# PCB_2.net
KiCad netlist of a schematic drawn in EAGLE
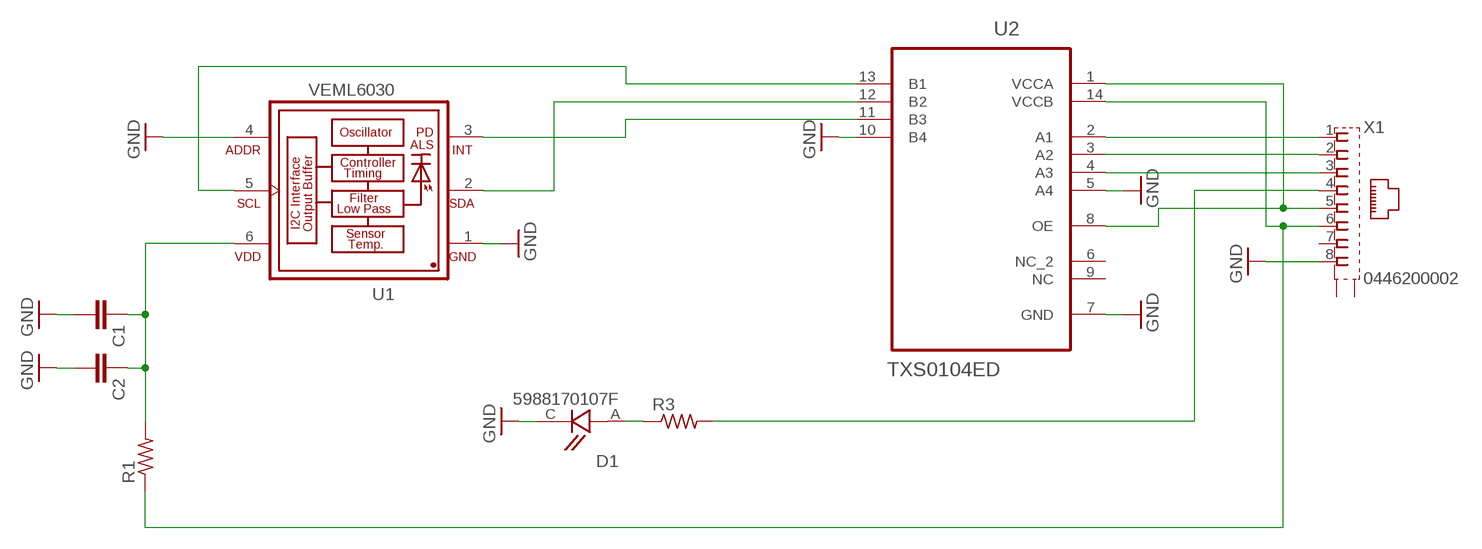
[diagram p0: schematic, sheet 1]

(export (version "E")
  (design (tool "Eeschema 10.0.6"))
  (components
    (comp (ref "C1")
      (value "C-EU025-024X044")
      (footprint "eagle-import:C025-024X044")
      (libsource (lib "eagle-import") (part "C-EU025-024X044"))
    )
    (comp (ref "C2")
      (value "C-EU025-024X044")
      (footprint "eagle-import:C025-024X044")
      (libsource (lib "eagle-import") (part "C-EU025-024X044"))
    )
    (comp (ref "D1")
      (value "5988170107F")
      (footprint "eagle-import:LEDC2012X70N")
      (fields (field (name "MF") "Dialight"))
      (libsource (lib "eagle-import") (part "5988170107F"))
    )
    (comp (ref "R1")
      (value "R-US_R0805")
      (footprint "eagle-import:R0805")
      (libsource (lib "eagle-import") (part "R-US_R0805"))
    )
    (comp (ref "R3")
      (value "R-US_R0805")
      (footprint "eagle-import:R0805")
      (libsource (lib "eagle-import") (part "R-US_R0805"))
    )
    (comp (ref "U1")
      (value "VEML6030")
      (footprint "eagle-import:VISHAY_VEML6030_2X2X0.87")
      (fields (field (name "MF") "Vishay"))
      (libsource (lib "eagle-import") (part "VEML6030"))
    )
    (comp (ref "U2")
      (value "TXS0104ED")
      (footprint "eagle-import:SOIC127P600X175-14N")
      (fields (field (name "MF") "Texas Instruments"))
      (libsource (lib "eagle-import") (part "TXS0104ED"))
    )
    (comp (ref "X1")
      (value "0446200002")
      (footprint "eagle-import:0446200002")
      (fields (field (name "MF") "Molex, LLC"))
      (libsource (lib "eagle-import") (part "0446200002"))
    )
  )
  (nets
    (net (code "1") (name "GND") (class "Default")
      (node (ref "C1") (pin "2") (pinfunction "2_2") (pintype "passive"))
      (node (ref "C2") (pin "2") (pinfunction "2_2") (pintype "passive"))
      (node (ref "D1") (pin "C") (pinfunction "C_C") (pintype "passive"))
      (node (ref "U1") (pin "1") (pinfunction "GND_1") (pintype "power_in"))
      (node (ref "U1") (pin "4") (pinfunction "ADDR_4") (pintype "bidirectional"))
      (node (ref "U2") (pin "10") (pinfunction "B4_10") (pintype "output"))
      (node (ref "U2") (pin "5") (pinfunction "A4_5") (pintype "input"))
      (node (ref "U2") (pin "7") (pinfunction "GND_7") (pintype "passive"))
      (node (ref "X1") (pin "8") (pinfunction "8_8") (pintype "passive"))
    )
    (net (code "2") (name "Net-(D1-PadA)") (class "Default")
      (node (ref "D1") (pin "A") (pinfunction "A_A") (pintype "passive"))
      (node (ref "R3") (pin "1") (pinfunction "1_1") (pintype "passive"))
    )
    (net (code "3") (name "Net-(R3-Pad2)") (class "Default")
      (node (ref "R3") (pin "2") (pinfunction "2_2") (pintype "passive"))
      (node (ref "X1") (pin "4") (pinfunction "4_4") (pintype "passive"))
    )
    (net (code "4") (name "Net-(U1-INT)") (class "Default")
      (node (ref "U1") (pin "3") (pinfunction "INT_3") (pintype "output"))
      (node (ref "U2") (pin "11") (pinfunction "B3_11") (pintype "output"))
    )
    (net (code "5") (name "Net-(U1-SCL)") (class "Default")
      (node (ref "U1") (pin "5") (pinfunction "SCL_5") (pintype "input"))
      (node (ref "U2") (pin "13") (pinfunction "B1_13") (pintype "output"))
    )
    (net (code "6") (name "Net-(U1-SDA)") (class "Default")
      (node (ref "U1") (pin "2") (pinfunction "SDA_2") (pintype "bidirectional"))
      (node (ref "U2") (pin "12") (pinfunction "B2_12") (pintype "output"))
    )
    (net (code "7") (name "Net-(U1-VDD)") (class "Default")
      (node (ref "C1") (pin "1") (pinfunction "1_1") (pintype "passive"))
      (node (ref "C2") (pin "1") (pinfunction "1_1") (pintype "passive"))
      (node (ref "R1") (pin "2") (pinfunction "2_2") (pintype "passive"))
      (node (ref "U1") (pin "6") (pinfunction "VDD_6") (pintype "power_in"))
    )
    (net (code "8") (name "Net-(U2-A1)") (class "Default")
      (node (ref "U2") (pin "2") (pinfunction "A1_2") (pintype "input"))
      (node (ref "X1") (pin "1") (pinfunction "1_1") (pintype "passive"))
    )
    (net (code "9") (name "Net-(U2-A2)") (class "Default")
      (node (ref "U2") (pin "3") (pinfunction "A2_3") (pintype "input"))
      (node (ref "X1") (pin "2") (pinfunction "2_2") (pintype "passive"))
    )
    (net (code "10") (name "Net-(U2-A3)") (class "Default")
      (node (ref "U2") (pin "4") (pinfunction "A3_4") (pintype "input"))
      (node (ref "X1") (pin "3") (pinfunction "3_3") (pintype "passive"))
    )
    (net (code "11") (name "Net-(U2-OE)") (class "Default")
      (node (ref "U2") (pin "1") (pinfunction "VCCA_1") (pintype "power_in"))
      (node (ref "U2") (pin "8") (pinfunction "OE_8") (pintype "input"))
      (node (ref "X1") (pin "5") (pinfunction "5_5") (pintype "passive"))
    )
    (net (code "12") (name "Net-(U2-VCCB)") (class "Default")
      (node (ref "R1") (pin "1") (pinfunction "1_1") (pintype "passive"))
      (node (ref "U2") (pin "14") (pinfunction "VCCB_14") (pintype "power_in"))
      (node (ref "X1") (pin "6") (pinfunction "6_6") (pintype "passive"))
    )
    (net (code "13") (name "unconnected-(U2-NC-Pad9)") (class "Default")
      (node (ref "U2") (pin "9") (pinfunction "NC_9") (pintype "no_connect"))
    )
    (net (code "14") (name "unconnected-(U2-NC_2-Pad6)") (class "Default")
      (node (ref "U2") (pin "6") (pinfunction "NC_2_6") (pintype "no_connect"))
    )
    (net (code "15") (name "unconnected-(X1-Pad7)") (class "Default")
      (node (ref "X1") (pin "7") (pinfunction "7_7") (pintype "passive"))
    )
    (net (code "16") (name "unconnected-(X1-S1-PadS@1)") (class "Default")
      (node (ref "X1") (pin "S@1") (pinfunction "S1_S@1") (pintype "passive"))
    )
    (net (code "17") (name "unconnected-(X1-S2-PadS@2)") (class "Default")
      (node (ref "X1") (pin "S@2") (pinfunction "S2_S@2") (pintype "passive"))
    )
  )
)
